# Esp32.net
KiCad netlist of a schematic drawn in Altium Designer
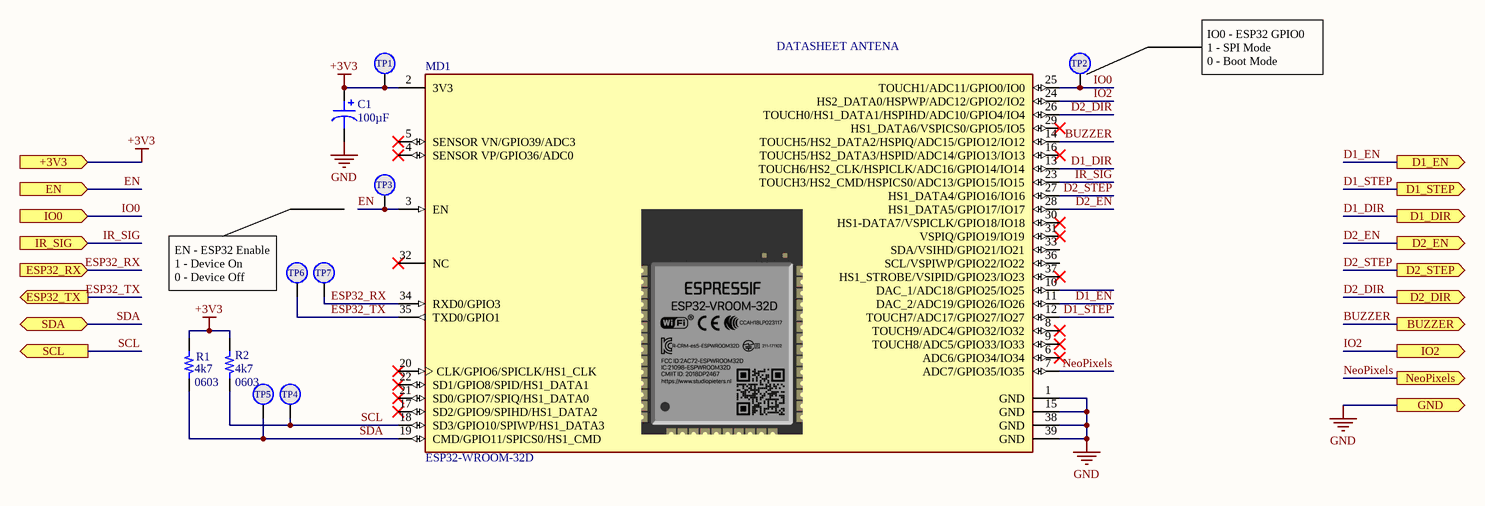
[diagram p0: Esp32.SchDoc]

(export (version "E")
  (design (tool "Eeschema 10.0.6"))
  (components
    (comp (ref "C1")
      (value "ALUM 100uF")
      (footprint "CAP ALSMD POLY 5.3MM H6.1MM")
      (description "CAP ALUM 100UF 4V 2000H")
      (fields
        (field (name "PART NUMBER") "MAL218497352E3")
        (field (name "MANUFACTURER") "Vishay Beyschlag/Draloric/BC Components")
        (field (name "CAPACITANCE") "100µF")
      )
      (libsource (lib "ControlBoard") (part "MAL218497352E3"))
    )
    (comp (ref "MD1")
      (value "ESP32-WROOM-32D")
      (footprint "FP-ESP32-WROOM-32D-MFG")
      (description "WIFI MODULE 32MBITS SPI FLASH")
      (fields
        (field (name "OCTOPART") "https://octopart.com/esp32-wroom-32d-espressif+systems-91040050")
        (field (name "MANUFACTURER") "Espressif Systems")
      )
      (libsource (lib "ControlBoard") (part "CMP-194065-000003-1"))
    )
    (comp (ref "R1")
      (value "4k7")
      (footprint "RESC1608X55X30NL15T15")
      (fields
        (field (name "TOLERANCE") "5%")
        (field (name "MANUFACTURER") "Panasonic")
        (field (name "MANUFACTURER PART NUMBER") "ERJ-3EKF4701V")
        (field (name "SIZE") "0603")
      )
      (libsource (lib "ControlBoard") (part "CMP-1012-00586-3"))
    )
    (comp (ref "R2")
      (value "4k7")
      (footprint "RESC1608X55X30NL15T15")
      (fields
        (field (name "TOLERANCE") "5%")
        (field (name "MANUFACTURER") "Panasonic")
        (field (name "MANUFACTURER PART NUMBER") "ERJ-3EKF4701V")
        (field (name "SIZE") "0603")
      )
      (libsource (lib "ControlBoard") (part "CMP-1012-00586-3"))
    )
    (comp (ref "TP1")
      (value "Test point")
      (footprint "TestPoint")
      (libsource (lib "ControlBoard") (part "TestPoint"))
    )
    (comp (ref "TP2")
      (value "Test point")
      (footprint "TestPoint")
      (libsource (lib "ControlBoard") (part "TestPoint"))
    )
    (comp (ref "TP3")
      (value "Test point")
      (footprint "TestPoint")
      (libsource (lib "ControlBoard") (part "TestPoint"))
    )
    (comp (ref "TP4")
      (value "Test point")
      (footprint "TestPoint")
      (libsource (lib "ControlBoard") (part "TestPoint"))
    )
    (comp (ref "TP5")
      (value "Test point")
      (footprint "TestPoint")
      (libsource (lib "ControlBoard") (part "TestPoint"))
    )
    (comp (ref "TP6")
      (value "Test point")
      (footprint "TestPoint")
      (libsource (lib "ControlBoard") (part "TestPoint"))
    )
    (comp (ref "TP7")
      (value "Test point")
      (footprint "TestPoint")
      (libsource (lib "ControlBoard") (part "TestPoint"))
    )
  )
  (nets
    (net (code "1") (name "+3V3") (class "Default")
      (node (ref "C1") (pin "1") (pinfunction "1_1") (pintype "passive"))
      (node (ref "MD1") (pin "2") (pinfunction "3V3_2") (pintype "power_in"))
      (node (ref "R1") (pin "1") (pinfunction "1_1") (pintype "passive"))
      (node (ref "R2") (pin "1") (pinfunction "1_1") (pintype "passive"))
      (node (ref "TP1") (pin "1") (pinfunction "_1_1") (pintype "passive"))
    )
    (net (code "2") (name "/BUZZER") (class "Default")
      (node (ref "MD1") (pin "14") (pinfunction "TOUCH5/HS2_DATA2/HSPIQ/ADC15/GPIO12/IO12_14") (pintype "bidirectional"))
    )
    (net (code "3") (name "/D1_DIR") (class "Default")
      (node (ref "MD1") (pin "13") (pinfunction "TOUCH6/HS2_CLK/HSPICLK/ADC16/GPIO14/IO14_13") (pintype "bidirectional"))
    )
    (net (code "4") (name "/D1_EN") (class "Default")
      (node (ref "MD1") (pin "11") (pinfunction "DAC_2/ADC19/GPIO26/IO26_11") (pintype "bidirectional"))
    )
    (net (code "5") (name "/D1_STEP") (class "Default")
      (node (ref "MD1") (pin "12") (pinfunction "TOUCH7/ADC17/GPIO27/IO27_12") (pintype "bidirectional"))
    )
    (net (code "6") (name "/D2_DIR") (class "Default")
      (node (ref "MD1") (pin "26") (pinfunction "TOUCH0/HS1_DATA1/HSPIHD/ADC10/GPIO4/IO4_26") (pintype "bidirectional"))
    )
    (net (code "7") (name "/D2_EN") (class "Default")
      (node (ref "MD1") (pin "28") (pinfunction "HS1_DATA5/GPIO17/IO17_28") (pintype "bidirectional"))
    )
    (net (code "8") (name "/D2_STEP") (class "Default")
      (node (ref "MD1") (pin "27") (pinfunction "HS1_DATA4/GPIO16/IO16_27") (pintype "bidirectional"))
    )
    (net (code "9") (name "/EN") (class "Default")
      (node (ref "MD1") (pin "3") (pinfunction "EN_3") (pintype "input"))
      (node (ref "TP3") (pin "1") (pinfunction "_1_1") (pintype "passive"))
    )
    (net (code "10") (name "/ESP32_RX") (class "Default")
      (node (ref "MD1") (pin "34") (pinfunction "RXD0/GPIO3_34") (pintype "input"))
      (node (ref "TP7") (pin "1") (pinfunction "_1_1") (pintype "passive"))
    )
    (net (code "11") (name "/ESP32_TX") (class "Default")
      (node (ref "MD1") (pin "35") (pinfunction "TXD0/GPIO1_35") (pintype "output"))
      (node (ref "TP6") (pin "1") (pinfunction "_1_1") (pintype "passive"))
    )
    (net (code "12") (name "/IO0") (class "Default")
      (node (ref "MD1") (pin "25") (pinfunction "TOUCH1/ADC11/GPIO0/IO0_25") (pintype "bidirectional"))
      (node (ref "TP2") (pin "1") (pinfunction "_1_1") (pintype "passive"))
    )
    (net (code "13") (name "/IO2") (class "Default")
      (node (ref "MD1") (pin "24") (pinfunction "HS2_DATA0/HSPWP/ADC12/GPIO2/IO2_24") (pintype "bidirectional"))
    )
    (net (code "14") (name "/IR_SIG") (class "Default")
      (node (ref "MD1") (pin "23") (pinfunction "TOUCH3/HS2_CMD/HSPICS0/ADC13/GPIO15/IO15_23") (pintype "bidirectional"))
    )
    (net (code "15") (name "/NeoPixels") (class "Default")
      (node (ref "MD1") (pin "7") (pinfunction "ADC7/GPIO35/IO35_7") (pintype "bidirectional"))
    )
    (net (code "16") (name "/SCL") (class "Default")
      (node (ref "MD1") (pin "18") (pinfunction "SD3/GPIO10/SPIWP/HS1_DATA3_18") (pintype "bidirectional"))
      (node (ref "R2") (pin "2") (pinfunction "2_2") (pintype "passive"))
      (node (ref "TP4") (pin "1") (pinfunction "_1_1") (pintype "passive"))
    )
    (net (code "17") (name "/SDA") (class "Default")
      (node (ref "MD1") (pin "19") (pinfunction "CMD/GPIO11/SPICS0/HS1_CMD_19") (pintype "bidirectional"))
      (node (ref "R1") (pin "2") (pinfunction "2_2") (pintype "passive"))
      (node (ref "TP5") (pin "1") (pinfunction "_1_1") (pintype "passive"))
    )
    (net (code "18") (name "GND") (class "Default")
      (node (ref "C1") (pin "2") (pinfunction "2_2") (pintype "passive"))
      (node (ref "MD1") (pin "1") (pinfunction "GND_1") (pintype "power_in"))
      (node (ref "MD1") (pin "15") (pinfunction "GND_15") (pintype "power_in"))
      (node (ref "MD1") (pin "38") (pinfunction "GND_38") (pintype "power_in"))
      (node (ref "MD1") (pin "39") (pinfunction "GND_39") (pintype "power_in"))
    )
    (net (code "19") (name "unconnected-(MD1-ADC6{slash}GPIO34{slash}IO34-Pad6)") (class "Default")
      (node (ref "MD1") (pin "6") (pinfunction "ADC6/GPIO34/IO34_6") (pintype "bidirectional+no_connect"))
    )
    (net (code "20") (name "unconnected-(MD1-CLK{slash}GPIO6{slash}SPICLK{slash}HS1_CLK-Pad20)") (class "Default")
      (node (ref "MD1") (pin "20") (pinfunction "CLK/GPIO6/SPICLK/HS1_CLK_20") (pintype "input+no_connect"))
    )
    (net (code "21") (name "unconnected-(MD1-DAC_1{slash}ADC18{slash}GPIO25{slash}IO25-Pad10)") (class "Default")
      (node (ref "MD1") (pin "10") (pinfunction "DAC_1/ADC18/GPIO25/IO25_10") (pintype "bidirectional"))
    )
    (net (code "22") (name "unconnected-(MD1-HS1-DATA7{slash}VSPICLK{slash}GPIO18{slash}IO18-Pad30)") (class "Default")
      (node (ref "MD1") (pin "30") (pinfunction "HS1-DATA7/VSPICLK/GPIO18/IO18_30") (pintype "bidirectional+no_connect"))
    )
    (net (code "23") (name "unconnected-(MD1-HS1_DATA6{slash}VSPICS0{slash}GPIO5{slash}IO5-Pad29)") (class "Default")
      (node (ref "MD1") (pin "29") (pinfunction "HS1_DATA6/VSPICS0/GPIO5/IO5_29") (pintype "bidirectional+no_connect"))
    )
    (net (code "24") (name "unconnected-(MD1-HS1_STROBE{slash}VSIPID{slash}GPIO23{slash}IO23-Pad37)") (class "Default")
      (node (ref "MD1") (pin "37") (pinfunction "HS1_STROBE/VSIPID/GPIO23/IO23_37") (pintype "bidirectional+no_connect"))
    )
    (net (code "25") (name "unconnected-(MD1-NC-Pad32)") (class "Default")
      (node (ref "MD1") (pin "32") (pinfunction "NC_32") (pintype "passive+no_connect"))
    )
    (net (code "26") (name "unconnected-(MD1-SCL{slash}VSPIWP{slash}GPIO22{slash}IO22-Pad36)") (class "Default")
      (node (ref "MD1") (pin "36") (pinfunction "SCL/VSPIWP/GPIO22/IO22_36") (pintype "bidirectional"))
    )
    (net (code "27") (name "unconnected-(MD1-SD0{slash}GPIO7{slash}SPIQ{slash}HS1_DATA0-Pad21)") (class "Default")
      (node (ref "MD1") (pin "21") (pinfunction "SD0/GPIO7/SPIQ/HS1_DATA0_21") (pintype "bidirectional+no_connect"))
    )
    (net (code "28") (name "unconnected-(MD1-SD1{slash}GPIO8{slash}SPID{slash}HS1_DATA1-Pad22)") (class "Default")
      (node (ref "MD1") (pin "22") (pinfunction "SD1/GPIO8/SPID/HS1_DATA1_22") (pintype "bidirectional+no_connect"))
    )
    (net (code "29") (name "unconnected-(MD1-SD2{slash}GPIO9{slash}SPIHD{slash}HS1_DATA2-Pad17)") (class "Default")
      (node (ref "MD1") (pin "17") (pinfunction "SD2/GPIO9/SPIHD/HS1_DATA2_17") (pintype "bidirectional+no_connect"))
    )
    (net (code "30") (name "unconnected-(MD1-SDA{slash}VSIHD{slash}GPIO21{slash}IO21-Pad33)") (class "Default")
      (node (ref "MD1") (pin "33") (pinfunction "SDA/VSIHD/GPIO21/IO21_33") (pintype "bidirectional"))
    )
    (net (code "31") (name "unconnected-(MD1-SENSOR_VN{slash}GPIO39{slash}ADC3-Pad5)") (class "Default")
      (node (ref "MD1") (pin "5") (pinfunction "SENSOR_VN/GPIO39/ADC3_5") (pintype "bidirectional+no_connect"))
    )
    (net (code "32") (name "unconnected-(MD1-SENSOR_VP{slash}GPIO36{slash}ADC0-Pad4)") (class "Default")
      (node (ref "MD1") (pin "4") (pinfunction "SENSOR_VP/GPIO36/ADC0_4") (pintype "bidirectional+no_connect"))
    )
    (net (code "33") (name "unconnected-(MD1-TOUCH5{slash}HS2_DATA3{slash}HSPID{slash}ADC14{slash}GPIO13{slash}IO13-Pad16)") (class "Default")
      (node (ref "MD1") (pin "16") (pinfunction "TOUCH5/HS2_DATA3/HSPID/ADC14/GPIO13/IO13_16") (pintype "bidirectional+no_connect"))
    )
    (net (code "34") (name "unconnected-(MD1-TOUCH8{slash}ADC5{slash}GPIO33{slash}IO33-Pad9)") (class "Default")
      (node (ref "MD1") (pin "9") (pinfunction "TOUCH8/ADC5/GPIO33/IO33_9") (pintype "bidirectional+no_connect"))
    )
    (net (code "35") (name "unconnected-(MD1-TOUCH9{slash}ADC4{slash}GPIO32{slash}IO32-Pad8)") (class "Default")
      (node (ref "MD1") (pin "8") (pinfunction "TOUCH9/ADC4/GPIO32/IO32_8") (pintype "bidirectional+no_connect"))
    )
    (net (code "36") (name "unconnected-(MD1-VSPIQ{slash}GPIO19{slash}IO19-Pad31)") (class "Default")
      (node (ref "MD1") (pin "31") (pinfunction "VSPIQ/GPIO19/IO19_31") (pintype "bidirectional+no_connect"))
    )
  )
)
